# usb2ttl.net
KiCad netlist of a schematic drawn in EAGLE
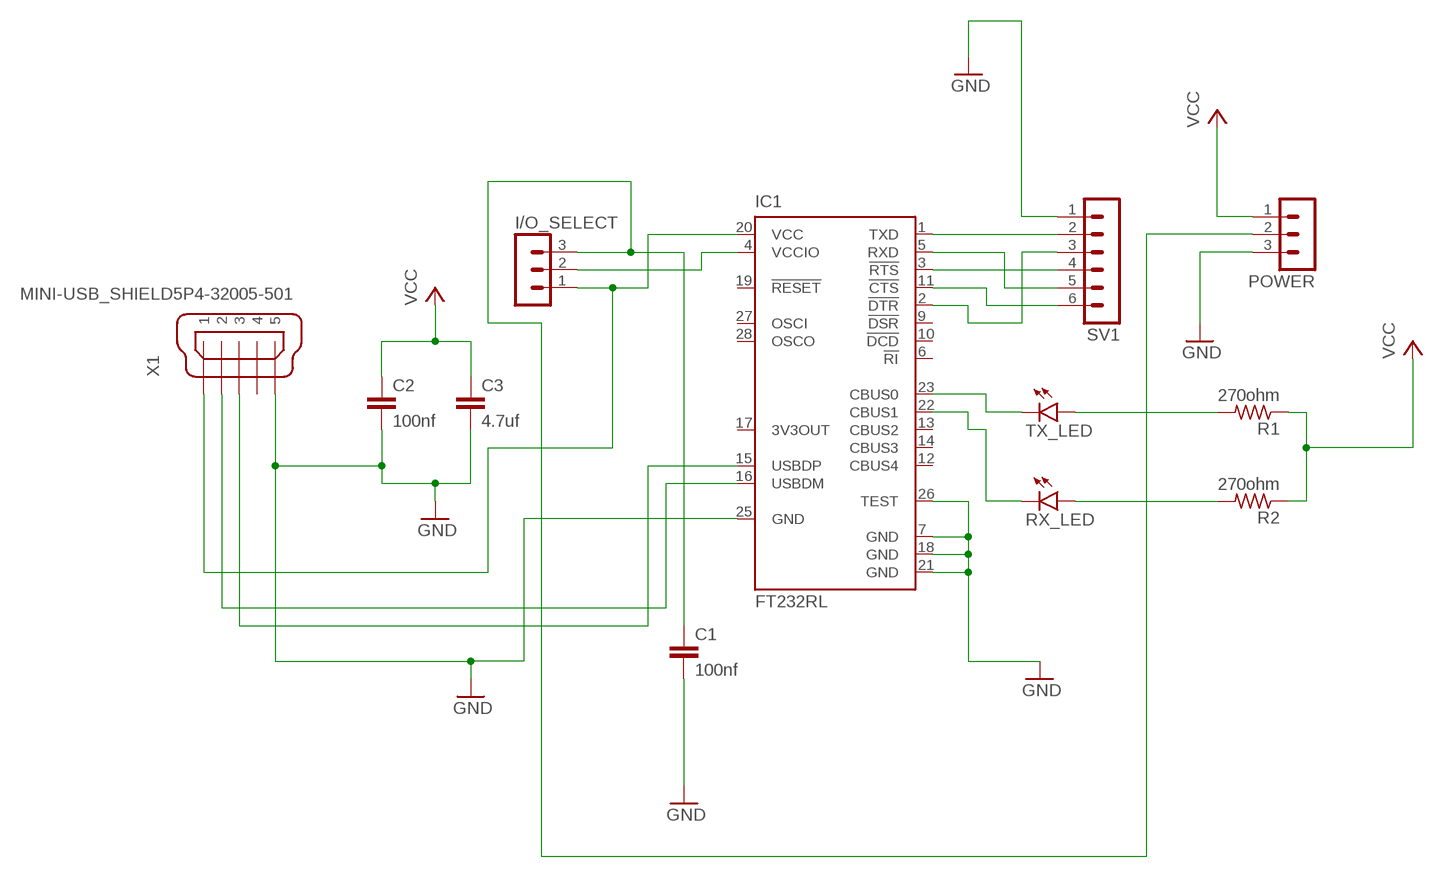
[diagram p0: schematic, sheet 1]

(export (version "E")
  (design (tool "Eeschema 10.0.6"))
  (components
    (comp (ref "C1")
      (value "100nf")
      (footprint "eagle-import:C2.5-3")
      (libsource (lib "eagle-import") (part "C2,5-3"))
    )
    (comp (ref "C2")
      (value "100nf")
      (footprint "eagle-import:C2.5-3")
      (libsource (lib "eagle-import") (part "C2,5-3"))
    )
    (comp (ref "C3")
      (value "4.7uf")
      (footprint "eagle-import:C2.5-3")
      (libsource (lib "eagle-import") (part "C2,5-3"))
    )
    (comp (ref "I/O_SELECT")
      (value "MA03-1")
      (footprint "eagle-import:MA03-1")
      (libsource (lib "eagle-import") (part "MA03-1"))
    )
    (comp (ref "IC1")
      (value "FT232RL")
      (footprint "eagle-import:SSOP28")
      (libsource (lib "eagle-import") (part "FT232RL"))
    )
    (comp (ref "POWER")
      (value "MA03-1")
      (footprint "eagle-import:MA03-1")
      (libsource (lib "eagle-import") (part "MA03-1"))
    )
    (comp (ref "R1")
      (value "270ohm")
      (footprint "eagle-import:0204_7")
      (libsource (lib "eagle-import") (part "R-US_0204/7"))
    )
    (comp (ref "R2")
      (value "270ohm")
      (footprint "eagle-import:0204_7")
      (libsource (lib "eagle-import") (part "R-US_0204/7"))
    )
    (comp (ref "RX_LED")
      (value "LED5MM")
      (footprint "eagle-import:LED5MM")
      (libsource (lib "eagle-import") (part "LED5MM"))
    )
    (comp (ref "SV1")
      (value "MA06-1")
      (footprint "eagle-import:MA06-1")
      (libsource (lib "eagle-import") (part "MA06-1"))
    )
    (comp (ref "TX_LED")
      (value "LED5MM")
      (footprint "eagle-import:LED5MM")
      (libsource (lib "eagle-import") (part "LED5MM"))
    )
    (comp (ref "X1")
      (value "MINI-USB_SHIELD5P4-32005-501")
      (footprint "eagle-import:32005-501")
      (libsource (lib "eagle-import") (part "MINI-USB_SHIELD5P4-32005-501"))
    )
  )
  (nets
    (net (code "1") (name "GND") (class "Default")
      (node (ref "C1") (pin "2") (pinfunction "2_2") (pintype "passive"))
      (node (ref "C2") (pin "2") (pinfunction "2_2") (pintype "passive"))
      (node (ref "C3") (pin "2") (pinfunction "2_2") (pintype "passive"))
      (node (ref "IC1") (pin "18") (pinfunction "GND_18") (pintype "power_in"))
      (node (ref "IC1") (pin "21") (pinfunction "GND_21") (pintype "power_in"))
      (node (ref "IC1") (pin "25") (pinfunction "GND_25") (pintype "power_in"))
      (node (ref "IC1") (pin "26") (pinfunction "TEST_26") (pintype "input"))
      (node (ref "IC1") (pin "7") (pinfunction "GND_7") (pintype "power_in"))
      (node (ref "POWER") (pin "3") (pinfunction "3_3") (pintype "passive"))
      (node (ref "SV1") (pin "1") (pinfunction "1_1") (pintype "passive"))
      (node (ref "X1") (pin "5") (pinfunction "5_5") (pintype "passive"))
    )
    (net (code "2") (name "Net-(C1-Pad1)") (class "Default")
      (node (ref "C1") (pin "1") (pinfunction "1_1") (pintype "passive"))
      (node (ref "I/O_SELECT") (pin "3") (pinfunction "3_3") (pintype "passive"))
      (node (ref "POWER") (pin "2") (pinfunction "2_2") (pintype "passive"))
    )
    (net (code "3") (name "Net-(IC1-CBUS0)") (class "Default")
      (node (ref "IC1") (pin "23") (pinfunction "CBUS0_23") (pintype "bidirectional"))
      (node (ref "TX_LED") (pin "K") (pinfunction "C_K") (pintype "passive"))
    )
    (net (code "4") (name "Net-(IC1-CBUS1)") (class "Default")
      (node (ref "IC1") (pin "22") (pinfunction "CBUS1_22") (pintype "bidirectional"))
      (node (ref "RX_LED") (pin "K") (pinfunction "C_K") (pintype "passive"))
    )
    (net (code "5") (name "Net-(IC1-RXD)") (class "Default")
      (node (ref "IC1") (pin "5") (pinfunction "RXD_5") (pintype "input"))
      (node (ref "SV1") (pin "5") (pinfunction "5_5") (pintype "passive"))
    )
    (net (code "6") (name "Net-(IC1-TXD)") (class "Default")
      (node (ref "IC1") (pin "1") (pinfunction "TXD_1") (pintype "output"))
      (node (ref "SV1") (pin "2") (pinfunction "2_2") (pintype "passive"))
    )
    (net (code "7") (name "Net-(IC1-USBDM)") (class "Default")
      (node (ref "IC1") (pin "16") (pinfunction "USBDM_16") (pintype "bidirectional"))
      (node (ref "X1") (pin "2") (pinfunction "2_2") (pintype "passive"))
    )
    (net (code "8") (name "Net-(IC1-USBDP)") (class "Default")
      (node (ref "IC1") (pin "15") (pinfunction "USBDP_15") (pintype "bidirectional"))
      (node (ref "X1") (pin "3") (pinfunction "3_3") (pintype "passive"))
    )
    (net (code "9") (name "Net-(IC1-VCC)") (class "Default")
      (node (ref "I/O_SELECT") (pin "1") (pinfunction "1_1") (pintype "passive"))
      (node (ref "IC1") (pin "20") (pinfunction "VCC_20") (pintype "power_in"))
      (node (ref "X1") (pin "1") (pinfunction "1_1") (pintype "passive"))
    )
    (net (code "10") (name "Net-(IC1-VCCIO)") (class "Default")
      (node (ref "I/O_SELECT") (pin "2") (pinfunction "2_2") (pintype "passive"))
      (node (ref "IC1") (pin "4") (pinfunction "VCCIO_4") (pintype "power_in"))
    )
    (net (code "11") (name "Net-(IC1-~{CTS})") (class "Default")
      (node (ref "IC1") (pin "11") (pinfunction "~{CTS}_11") (pintype "input"))
      (node (ref "SV1") (pin "6") (pinfunction "6_6") (pintype "passive"))
    )
    (net (code "12") (name "Net-(IC1-~{DTR})") (class "Default")
      (node (ref "IC1") (pin "2") (pinfunction "~{DTR}_2") (pintype "output"))
      (node (ref "SV1") (pin "3") (pinfunction "3_3") (pintype "passive"))
    )
    (net (code "13") (name "Net-(IC1-~{RTS})") (class "Default")
      (node (ref "IC1") (pin "3") (pinfunction "~{RTS}_3") (pintype "output"))
      (node (ref "SV1") (pin "4") (pinfunction "4_4") (pintype "passive"))
    )
    (net (code "14") (name "Net-(R1-Pad2)") (class "Default")
      (node (ref "R1") (pin "2") (pinfunction "2_2") (pintype "passive"))
      (node (ref "TX_LED") (pin "A") (pinfunction "A_A") (pintype "passive"))
    )
    (net (code "15") (name "Net-(R2-Pad2)") (class "Default")
      (node (ref "R2") (pin "2") (pinfunction "2_2") (pintype "passive"))
      (node (ref "RX_LED") (pin "A") (pinfunction "A_A") (pintype "passive"))
    )
    (net (code "16") (name "VCC") (class "Default")
      (node (ref "C2") (pin "1") (pinfunction "1_1") (pintype "passive"))
      (node (ref "C3") (pin "1") (pinfunction "1_1") (pintype "passive"))
      (node (ref "POWER") (pin "1") (pinfunction "1_1") (pintype "passive"))
      (node (ref "R1") (pin "1") (pinfunction "1_1") (pintype "passive"))
      (node (ref "R2") (pin "1") (pinfunction "1_1") (pintype "passive"))
    )
    (net (code "17") (name "unconnected-(IC1-3V3OUT-Pad17)") (class "Default")
      (node (ref "IC1") (pin "17") (pinfunction "3V3OUT_17") (pintype "output"))
    )
    (net (code "18") (name "unconnected-(IC1-CBUS2-Pad13)") (class "Default")
      (node (ref "IC1") (pin "13") (pinfunction "CBUS2_13") (pintype "bidirectional"))
    )
    (net (code "19") (name "unconnected-(IC1-CBUS3-Pad14)") (class "Default")
      (node (ref "IC1") (pin "14") (pinfunction "CBUS3_14") (pintype "bidirectional"))
    )
    (net (code "20") (name "unconnected-(IC1-CBUS4-Pad12)") (class "Default")
      (node (ref "IC1") (pin "12") (pinfunction "CBUS4_12") (pintype "bidirectional"))
    )
    (net (code "21") (name "unconnected-(IC1-OSCI-Pad27)") (class "Default")
      (node (ref "IC1") (pin "27") (pinfunction "OSCI_27") (pintype "input"))
    )
    (net (code "22") (name "unconnected-(IC1-OSCO-Pad28)") (class "Default")
      (node (ref "IC1") (pin "28") (pinfunction "OSCO_28") (pintype "output"))
    )
    (net (code "23") (name "unconnected-(IC1-~{DCD}-Pad10)") (class "Default")
      (node (ref "IC1") (pin "10") (pinfunction "~{DCD}_10") (pintype "input"))
    )
    (net (code "24") (name "unconnected-(IC1-~{DSR}-Pad9)") (class "Default")
      (node (ref "IC1") (pin "9") (pinfunction "~{DSR}_9") (pintype "input"))
    )
    (net (code "25") (name "unconnected-(IC1-~{RESET}-Pad19)") (class "Default")
      (node (ref "IC1") (pin "19") (pinfunction "~{RESET}_19") (pintype "input"))
    )
    (net (code "26") (name "unconnected-(IC1-~{RI}-Pad6)") (class "Default")
      (node (ref "IC1") (pin "6") (pinfunction "~{RI}_6") (pintype "input"))
    )
    (net (code "27") (name "unconnected-(X1-Pad4)") (class "Default")
      (node (ref "X1") (pin "4") (pinfunction "4_4") (pintype "passive"))
    )
  )
)
